# southbridge.net
KiCad netlist of a schematic drawn in EAGLE
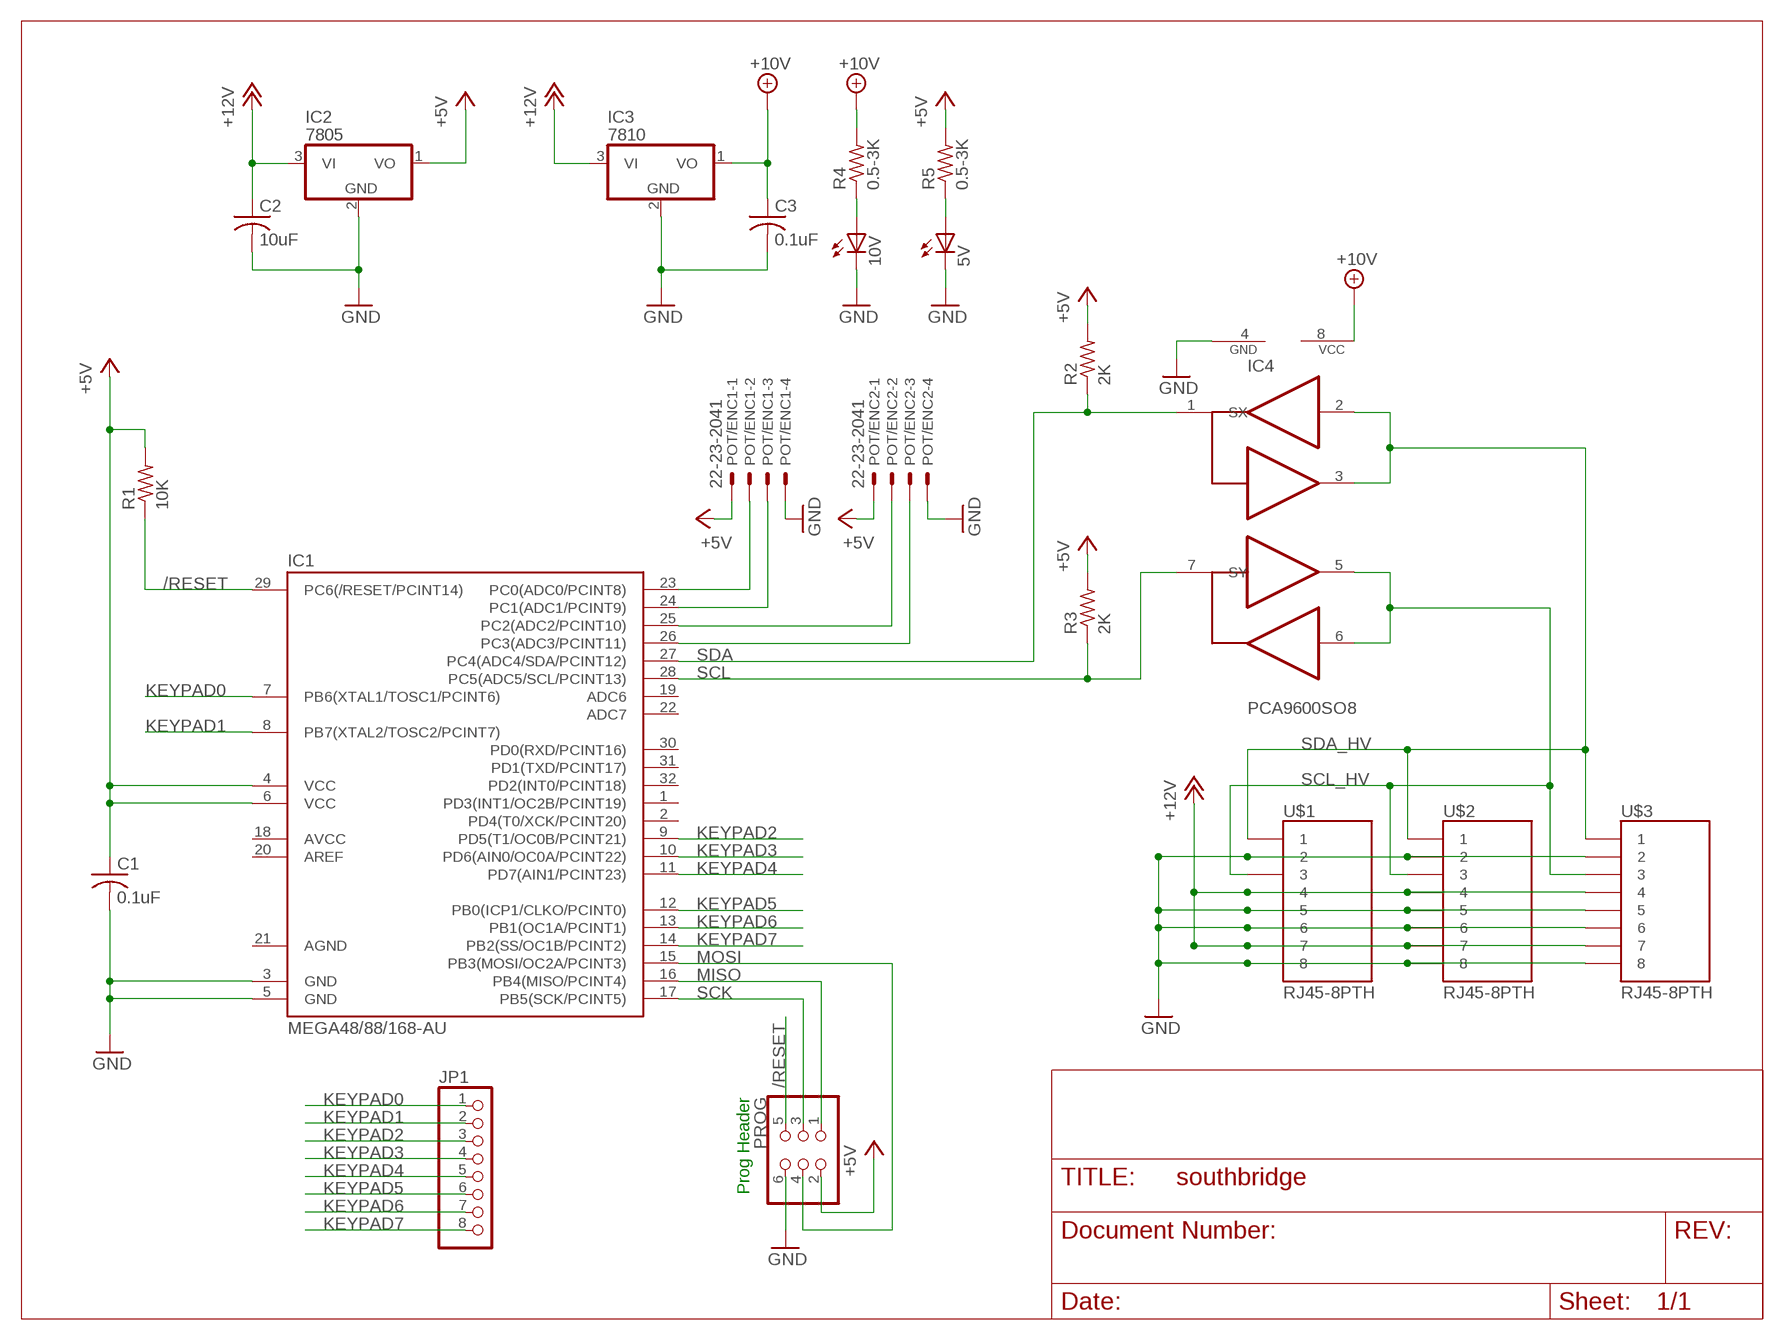
[diagram p0: schematic, sheet 1]

(export (version "E")
  (design (tool "Eeschema 10.0.6"))
  (components
    (comp (ref "5V")
      (value "LED3MM")
      (footprint "eagle-import:LED3MM")
      (libsource (lib "eagle-import") (part "LED3MM"))
    )
    (comp (ref "10V")
      (value "LED3MM")
      (footprint "eagle-import:LED3MM")
      (libsource (lib "eagle-import") (part "LED3MM"))
    )
    (comp (ref "C1")
      (value "0.1uF")
      (footprint "eagle-import:C025-025X050")
      (libsource (lib "eagle-import") (part "C-US025-025X050"))
    )
    (comp (ref "C2")
      (value "10uF")
      (footprint "eagle-import:C025-025X050")
      (libsource (lib "eagle-import") (part "C-US025-025X050"))
    )
    (comp (ref "C3")
      (value "0.1uF")
      (footprint "eagle-import:C025-025X050")
      (libsource (lib "eagle-import") (part "C-US025-025X050"))
    )
    (comp (ref "IC1")
      (value "MEGA48/88/168-AU")
      (footprint "eagle-import:TQFP32-08")
      (libsource (lib "eagle-import") (part "MEGA48/88/168-AU"))
    )
    (comp (ref "IC2")
      (value "7805")
      (footprint "eagle-import:TO92")
      (libsource (lib "eagle-import") (part "78ZL05"))
    )
    (comp (ref "IC3")
      (value "7810")
      (footprint "eagle-import:TO92")
      (libsource (lib "eagle-import") (part "78ZL05"))
    )
    (comp (ref "IC4")
      (value "PCA9600SO8")
      (footprint "eagle-import:SO08")
      (libsource (lib "eagle-import") (part "PCA9600SO8"))
    )
    (comp (ref "JP1")
      (value "HEADER-1X8ROUND")
      (footprint "eagle-import:1X08_ROUND")
      (libsource (lib "eagle-import") (part "HEADER-1X8ROUND"))
    )
    (comp (ref "POT/ENC1")
      (value "22-23-2041")
      (footprint "eagle-import:22-23-2041")
      (fields (field (name "MF") "MOLEX"))
      (libsource (lib "eagle-import") (part "22-23-2041"))
    )
    (comp (ref "POT/ENC2")
      (value "22-23-2041")
      (footprint "eagle-import:22-23-2041")
      (fields (field (name "MF") "MOLEX"))
      (libsource (lib "eagle-import") (part "22-23-2041"))
    )
    (comp (ref "PROG")
      (value "PINHD-2X3")
      (footprint "eagle-import:2X03")
      (libsource (lib "eagle-import") (part "PINHD-2X3"))
    )
    (comp (ref "R1")
      (value "10K")
      (footprint "eagle-import:0204_5")
      (libsource (lib "eagle-import") (part "R-US_0204/5"))
    )
    (comp (ref "R2")
      (value "2K")
      (footprint "eagle-import:0204_5")
      (libsource (lib "eagle-import") (part "R-US_0204/5"))
    )
    (comp (ref "R3")
      (value "2K")
      (footprint "eagle-import:0204_5")
      (libsource (lib "eagle-import") (part "R-US_0204/5"))
    )
    (comp (ref "R4")
      (value "0.5-3K")
      (footprint "eagle-import:0204_5")
      (libsource (lib "eagle-import") (part "R-US_0204/5"))
    )
    (comp (ref "R5")
      (value "0.5-3K")
      (footprint "eagle-import:0204_5")
      (libsource (lib "eagle-import") (part "R-US_0204/5"))
    )
    (comp (ref "U$1")
      (value "RJ45-8PTH")
      (footprint "eagle-import:RJ45-8")
      (libsource (lib "eagle-import") (part "RJ45-8PTH"))
    )
    (comp (ref "U$2")
      (value "RJ45-8PTH")
      (footprint "eagle-import:RJ45-8")
      (libsource (lib "eagle-import") (part "RJ45-8PTH"))
    )
    (comp (ref "U$3")
      (value "RJ45-8PTH")
      (footprint "eagle-import:RJ45-8")
      (libsource (lib "eagle-import") (part "RJ45-8PTH"))
    )
  )
  (nets
    (net (code "1") (name "+5V") (class "Default")
      (node (ref "C1") (pin "1") (pinfunction "1_1") (pintype "passive"))
      (node (ref "IC1") (pin "4") (pinfunction "VCC_4") (pintype "power_in"))
      (node (ref "IC1") (pin "6") (pinfunction "VCC_6") (pintype "power_in"))
      (node (ref "IC2") (pin "1") (pinfunction "VO_1") (pintype "passive"))
      (node (ref "POT/ENC1") (pin "1") (pinfunction "S_1") (pintype "passive"))
      (node (ref "POT/ENC2") (pin "1") (pinfunction "S_1") (pintype "passive"))
      (node (ref "PROG") (pin "2") (pinfunction "2_2") (pintype "passive"))
      (node (ref "R1") (pin "2") (pinfunction "2_2") (pintype "passive"))
      (node (ref "R2") (pin "2") (pinfunction "2_2") (pintype "passive"))
      (node (ref "R3") (pin "2") (pinfunction "2_2") (pintype "passive"))
      (node (ref "R5") (pin "2") (pinfunction "2_2") (pintype "passive"))
    )
    (net (code "2") (name "+10V") (class "Default")
      (node (ref "C3") (pin "1") (pinfunction "1_1") (pintype "passive"))
      (node (ref "IC3") (pin "1") (pinfunction "VO_1") (pintype "passive"))
      (node (ref "IC4") (pin "8") (pinfunction "VCC_8") (pintype "power_in"))
      (node (ref "R4") (pin "2") (pinfunction "2_2") (pintype "passive"))
    )
    (net (code "3") (name "+12V") (class "Default")
      (node (ref "C2") (pin "1") (pinfunction "1_1") (pintype "passive"))
      (node (ref "IC2") (pin "3") (pinfunction "VI_3") (pintype "input"))
      (node (ref "IC3") (pin "3") (pinfunction "VI_3") (pintype "input"))
      (node (ref "U$1") (pin "4") (pinfunction "4_4") (pintype "bidirectional"))
      (node (ref "U$1") (pin "7") (pinfunction "7_7") (pintype "bidirectional"))
      (node (ref "U$2") (pin "4") (pinfunction "4_4") (pintype "bidirectional"))
      (node (ref "U$2") (pin "7") (pinfunction "7_7") (pintype "bidirectional"))
      (node (ref "U$3") (pin "4") (pinfunction "4_4") (pintype "bidirectional"))
      (node (ref "U$3") (pin "7") (pinfunction "7_7") (pintype "bidirectional"))
    )
    (net (code "4") (name "/AGND") (class "Default")
      (node (ref "IC1") (pin "21") (pinfunction "AGND_21") (pintype "power_in"))
    )
    (net (code "5") (name "/KEYPAD0") (class "Default")
      (node (ref "IC1") (pin "7") (pinfunction "PB6(XTAL1/TOSC1/PCINT6)_7") (pintype "bidirectional"))
      (node (ref "JP1") (pin "1") (pinfunction "1_1") (pintype "passive"))
    )
    (net (code "6") (name "/KEYPAD1") (class "Default")
      (node (ref "IC1") (pin "8") (pinfunction "PB7(XTAL2/TOSC2/PCINT7)_8") (pintype "bidirectional"))
      (node (ref "JP1") (pin "2") (pinfunction "2_2") (pintype "passive"))
    )
    (net (code "7") (name "/KEYPAD2") (class "Default")
      (node (ref "IC1") (pin "9") (pinfunction "PD5(T1/OC0B/PCINT21)_9") (pintype "bidirectional"))
      (node (ref "JP1") (pin "3") (pinfunction "3_3") (pintype "passive"))
    )
    (net (code "8") (name "/KEYPAD3") (class "Default")
      (node (ref "IC1") (pin "10") (pinfunction "PD6(AIN0/OC0A/PCINT22)_10") (pintype "bidirectional"))
      (node (ref "JP1") (pin "4") (pinfunction "4_4") (pintype "passive"))
    )
    (net (code "9") (name "/KEYPAD4") (class "Default")
      (node (ref "IC1") (pin "11") (pinfunction "PD7(AIN1/PCINT23)_11") (pintype "bidirectional"))
      (node (ref "JP1") (pin "5") (pinfunction "5_5") (pintype "passive"))
    )
    (net (code "10") (name "/KEYPAD5") (class "Default")
      (node (ref "IC1") (pin "12") (pinfunction "PB0(ICP1/CLKO/PCINT0)_12") (pintype "bidirectional"))
      (node (ref "JP1") (pin "6") (pinfunction "6_6") (pintype "passive"))
    )
    (net (code "11") (name "/KEYPAD6") (class "Default")
      (node (ref "IC1") (pin "13") (pinfunction "PB1(OC1A/PCINT1)_13") (pintype "bidirectional"))
      (node (ref "JP1") (pin "7") (pinfunction "7_7") (pintype "passive"))
    )
    (net (code "12") (name "/KEYPAD7") (class "Default")
      (node (ref "IC1") (pin "14") (pinfunction "PB2(SS/OC1B/PCINT2)_14") (pintype "bidirectional"))
      (node (ref "JP1") (pin "8") (pinfunction "8_8") (pintype "passive"))
    )
    (net (code "13") (name "/MISO") (class "Default")
      (node (ref "IC1") (pin "16") (pinfunction "PB4(MISO/PCINT4)_16") (pintype "bidirectional"))
      (node (ref "PROG") (pin "1") (pinfunction "1_1") (pintype "passive"))
    )
    (net (code "14") (name "/MOSI") (class "Default")
      (node (ref "IC1") (pin "15") (pinfunction "PB3(MOSI/OC2A/PCINT3)_15") (pintype "bidirectional"))
      (node (ref "PROG") (pin "4") (pinfunction "4_4") (pintype "passive"))
    )
    (net (code "15") (name "/SCK") (class "Default")
      (node (ref "IC1") (pin "17") (pinfunction "PB5(SCK/PCINT5)_17") (pintype "bidirectional"))
      (node (ref "PROG") (pin "3") (pinfunction "3_3") (pintype "passive"))
    )
    (net (code "16") (name "/SCL") (class "Default")
      (node (ref "IC1") (pin "28") (pinfunction "PC5(ADC5/SCL/PCINT13)_28") (pintype "bidirectional"))
      (node (ref "IC4") (pin "7") (pinfunction "SY_7") (pintype "bidirectional"))
      (node (ref "R3") (pin "1") (pinfunction "1_1") (pintype "passive"))
    )
    (net (code "17") (name "/SCL_HV") (class "Default")
      (node (ref "IC4") (pin "5") (pinfunction "TY_5") (pintype "output"))
      (node (ref "IC4") (pin "6") (pinfunction "RY_6") (pintype "input"))
      (node (ref "U$1") (pin "3") (pinfunction "3_3") (pintype "bidirectional"))
      (node (ref "U$2") (pin "3") (pinfunction "3_3") (pintype "bidirectional"))
      (node (ref "U$3") (pin "3") (pinfunction "3_3") (pintype "bidirectional"))
    )
    (net (code "18") (name "/SDA") (class "Default")
      (node (ref "IC1") (pin "27") (pinfunction "PC4(ADC4/SDA/PCINT12)_27") (pintype "bidirectional"))
      (node (ref "IC4") (pin "1") (pinfunction "SX_1") (pintype "bidirectional"))
      (node (ref "R2") (pin "1") (pinfunction "1_1") (pintype "passive"))
    )
    (net (code "19") (name "/SDA_HV") (class "Default")
      (node (ref "IC4") (pin "2") (pinfunction "RX_2") (pintype "input"))
      (node (ref "IC4") (pin "3") (pinfunction "TX_3") (pintype "output"))
      (node (ref "U$1") (pin "1") (pinfunction "1_1") (pintype "bidirectional"))
      (node (ref "U$2") (pin "1") (pinfunction "1_1") (pintype "bidirectional"))
      (node (ref "U$3") (pin "1") (pinfunction "1_1") (pintype "bidirectional"))
    )
    (net (code "20") (name "/{slash}RESET") (class "Default")
      (node (ref "IC1") (pin "29") (pinfunction "PC6(/RESET/PCINT14)_29") (pintype "bidirectional"))
      (node (ref "PROG") (pin "5") (pinfunction "5_5") (pintype "passive"))
      (node (ref "R1") (pin "1") (pinfunction "1_1") (pintype "passive"))
    )
    (net (code "21") (name "GND") (class "Default")
      (node (ref "10V") (pin "K") (pinfunction "C_K") (pintype "passive"))
      (node (ref "5V") (pin "K") (pinfunction "C_K") (pintype "passive"))
      (node (ref "C1") (pin "2") (pinfunction "2_2") (pintype "passive"))
      (node (ref "C2") (pin "2") (pinfunction "2_2") (pintype "passive"))
      (node (ref "C3") (pin "2") (pinfunction "2_2") (pintype "passive"))
      (node (ref "IC1") (pin "3") (pinfunction "GND_3") (pintype "power_in"))
      (node (ref "IC1") (pin "5") (pinfunction "GND_5") (pintype "power_in"))
      (node (ref "IC2") (pin "2") (pinfunction "GND_2") (pintype "passive"))
      (node (ref "IC3") (pin "2") (pinfunction "GND_2") (pintype "passive"))
      (node (ref "IC4") (pin "4") (pinfunction "GND_4") (pintype "power_in"))
      (node (ref "POT/ENC1") (pin "4") (pinfunction "S_4") (pintype "passive"))
      (node (ref "POT/ENC2") (pin "4") (pinfunction "S_4") (pintype "passive"))
      (node (ref "PROG") (pin "6") (pinfunction "6_6") (pintype "passive"))
      (node (ref "U$1") (pin "2") (pinfunction "2_2") (pintype "bidirectional"))
      (node (ref "U$1") (pin "5") (pinfunction "5_5") (pintype "bidirectional"))
      (node (ref "U$1") (pin "6") (pinfunction "6_6") (pintype "bidirectional"))
      (node (ref "U$1") (pin "8") (pinfunction "8_8") (pintype "bidirectional"))
      (node (ref "U$2") (pin "2") (pinfunction "2_2") (pintype "bidirectional"))
      (node (ref "U$2") (pin "5") (pinfunction "5_5") (pintype "bidirectional"))
      (node (ref "U$2") (pin "6") (pinfunction "6_6") (pintype "bidirectional"))
      (node (ref "U$2") (pin "8") (pinfunction "8_8") (pintype "bidirectional"))
      (node (ref "U$3") (pin "2") (pinfunction "2_2") (pintype "bidirectional"))
      (node (ref "U$3") (pin "5") (pinfunction "5_5") (pintype "bidirectional"))
      (node (ref "U$3") (pin "6") (pinfunction "6_6") (pintype "bidirectional"))
      (node (ref "U$3") (pin "8") (pinfunction "8_8") (pintype "bidirectional"))
    )
    (net (code "22") (name "Net-(5V-PadA)") (class "Default")
      (node (ref "5V") (pin "A") (pinfunction "A_A") (pintype "passive"))
      (node (ref "R5") (pin "1") (pinfunction "1_1") (pintype "passive"))
    )
    (net (code "23") (name "Net-(10V-PadA)") (class "Default")
      (node (ref "10V") (pin "A") (pinfunction "A_A") (pintype "passive"))
      (node (ref "R4") (pin "1") (pinfunction "1_1") (pintype "passive"))
    )
    (net (code "24") (name "Net-(IC1-PC0(ADC0{slash}PCINT8))") (class "Default")
      (node (ref "IC1") (pin "23") (pinfunction "PC0(ADC0/PCINT8)_23") (pintype "bidirectional"))
      (node (ref "POT/ENC1") (pin "2") (pinfunction "S_2") (pintype "passive"))
    )
    (net (code "25") (name "Net-(IC1-PC1(ADC1{slash}PCINT9))") (class "Default")
      (node (ref "IC1") (pin "24") (pinfunction "PC1(ADC1/PCINT9)_24") (pintype "bidirectional"))
      (node (ref "POT/ENC1") (pin "3") (pinfunction "S_3") (pintype "passive"))
    )
    (net (code "26") (name "Net-(IC1-PC2(ADC2{slash}PCINT10))") (class "Default")
      (node (ref "IC1") (pin "25") (pinfunction "PC2(ADC2/PCINT10)_25") (pintype "bidirectional"))
      (node (ref "POT/ENC2") (pin "2") (pinfunction "S_2") (pintype "passive"))
    )
    (net (code "27") (name "Net-(IC1-PC3(ADC3{slash}PCINT11))") (class "Default")
      (node (ref "IC1") (pin "26") (pinfunction "PC3(ADC3/PCINT11)_26") (pintype "bidirectional"))
      (node (ref "POT/ENC2") (pin "3") (pinfunction "S_3") (pintype "passive"))
    )
    (net (code "28") (name "unconnected-(IC1-ADC6-Pad19)") (class "Default")
      (node (ref "IC1") (pin "19") (pinfunction "ADC6_19") (pintype "passive"))
    )
    (net (code "29") (name "unconnected-(IC1-ADC7-Pad22)") (class "Default")
      (node (ref "IC1") (pin "22") (pinfunction "ADC7_22") (pintype "passive"))
    )
    (net (code "30") (name "unconnected-(IC1-AREF-Pad20)") (class "Default")
      (node (ref "IC1") (pin "20") (pinfunction "AREF_20") (pintype "passive"))
    )
    (net (code "31") (name "unconnected-(IC1-AVCC-Pad18)") (class "Default")
      (node (ref "IC1") (pin "18") (pinfunction "AVCC_18") (pintype "passive"))
    )
    (net (code "32") (name "unconnected-(IC1-PD0(RXD{slash}PCINT16)-Pad30)") (class "Default")
      (node (ref "IC1") (pin "30") (pinfunction "PD0(RXD/PCINT16)_30") (pintype "bidirectional"))
    )
    (net (code "33") (name "unconnected-(IC1-PD1(TXD{slash}PCINT17)-Pad31)") (class "Default")
      (node (ref "IC1") (pin "31") (pinfunction "PD1(TXD/PCINT17)_31") (pintype "bidirectional"))
    )
    (net (code "34") (name "unconnected-(IC1-PD2(INT0{slash}PCINT18)-Pad32)") (class "Default")
      (node (ref "IC1") (pin "32") (pinfunction "PD2(INT0/PCINT18)_32") (pintype "bidirectional"))
    )
    (net (code "35") (name "unconnected-(IC1-PD3(INT1{slash}OC2B{slash}PCINT19)-Pad1)") (class "Default")
      (node (ref "IC1") (pin "1") (pinfunction "PD3(INT1/OC2B/PCINT19)_1") (pintype "bidirectional"))
    )
    (net (code "36") (name "unconnected-(IC1-PD4(T0{slash}XCK{slash}PCINT20)-Pad2)") (class "Default")
      (node (ref "IC1") (pin "2") (pinfunction "PD4(T0/XCK/PCINT20)_2") (pintype "bidirectional"))
    )
  )
)
